# U64_KB_Ada.net
KiCad netlist of a schematic drawn in EAGLE
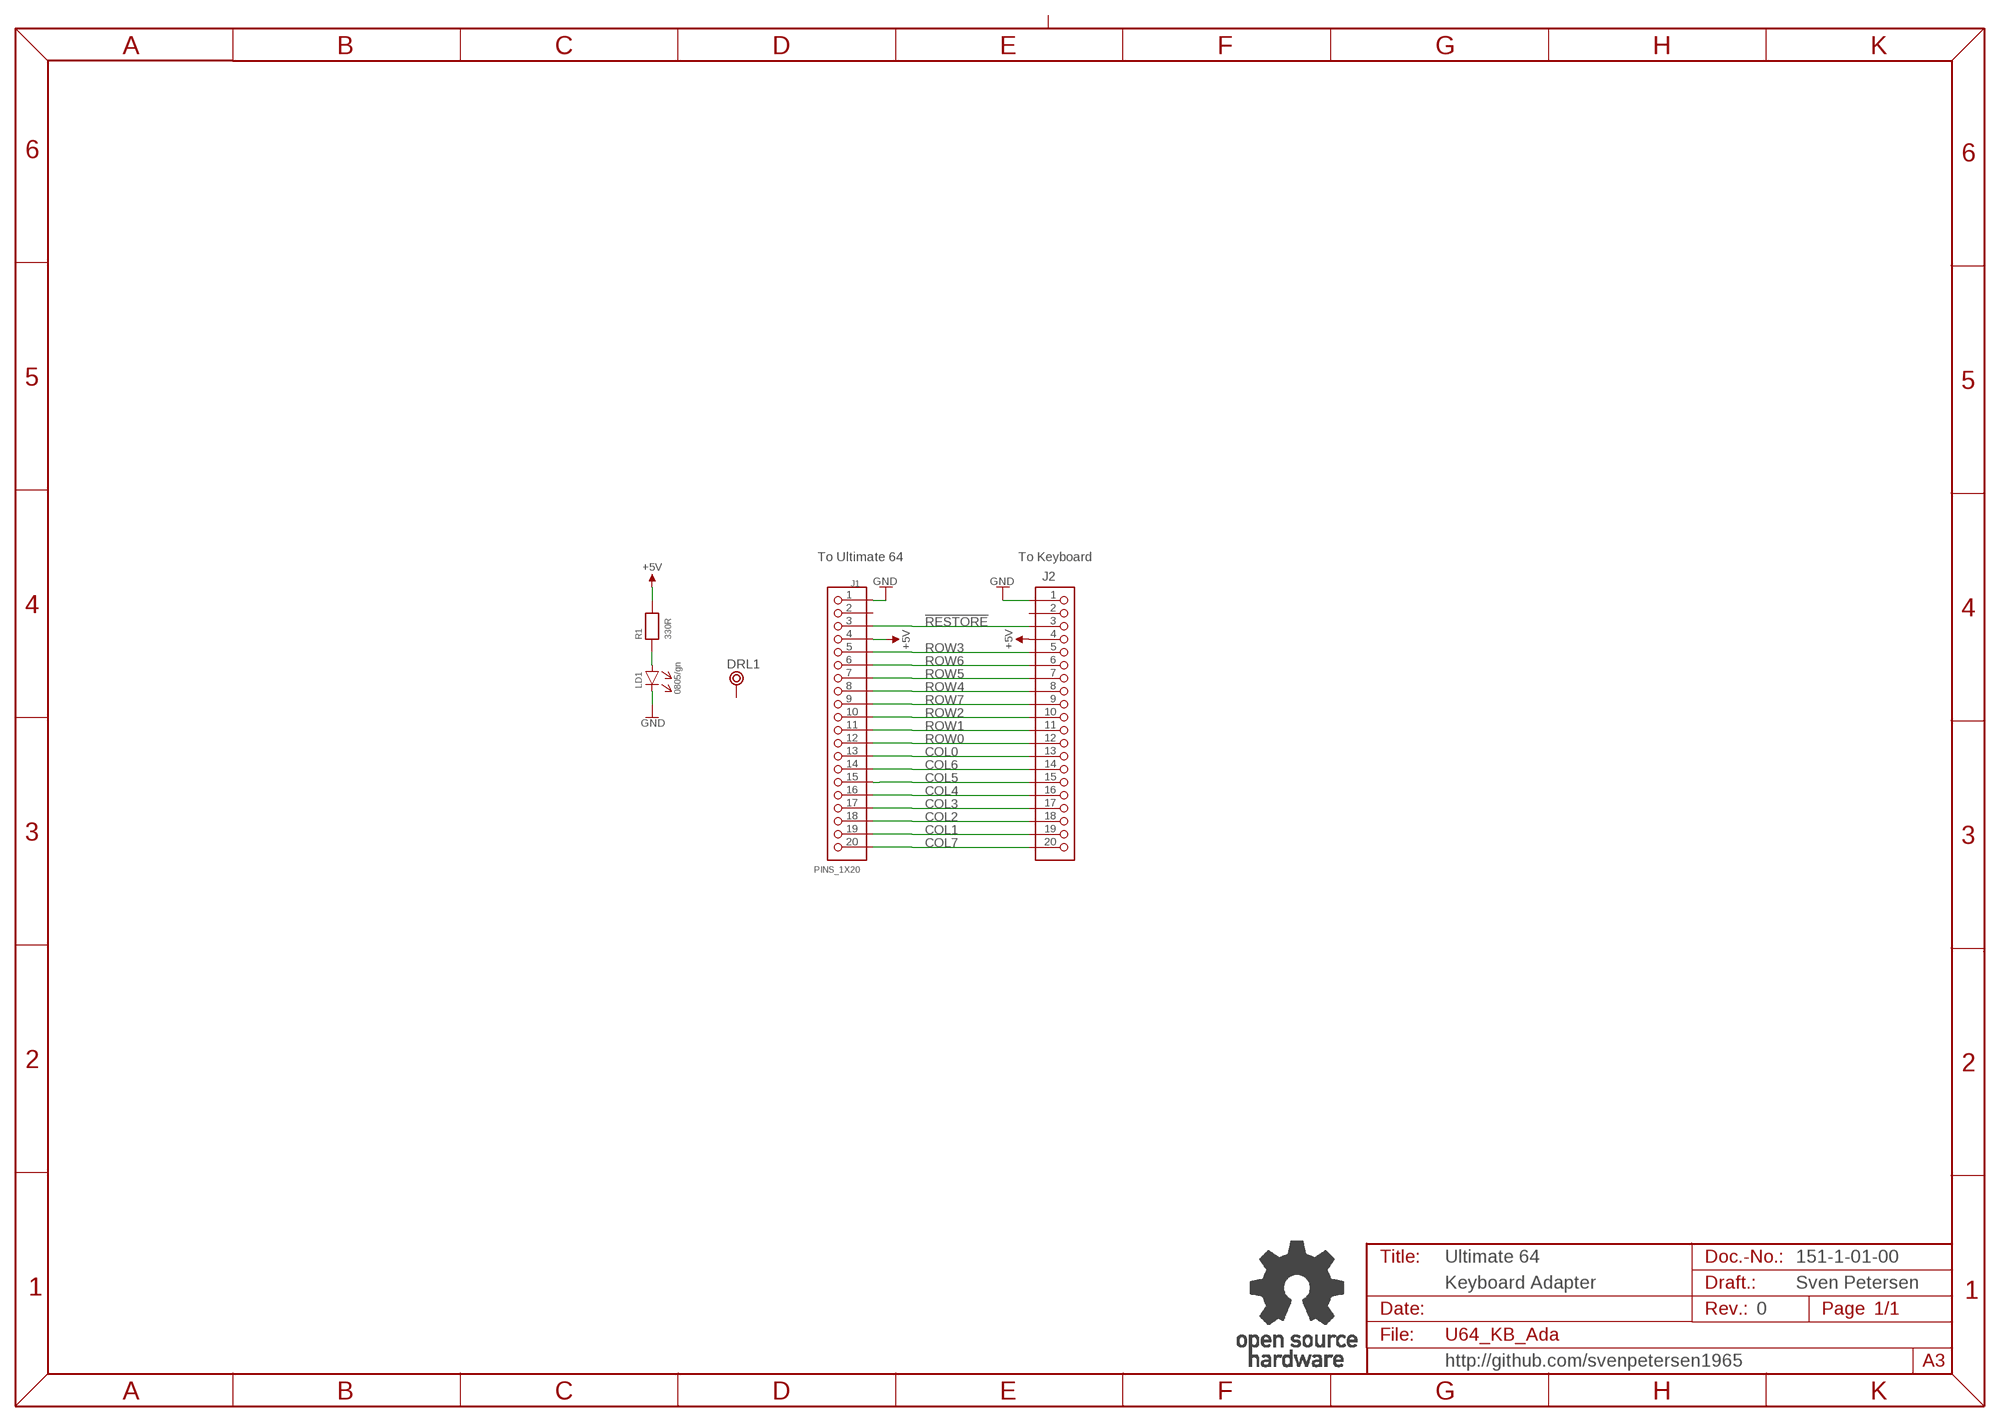
[diagram p0: schematic, sheet 1]

(export (version "E")
  (design (tool "Eeschema 10.0.6"))
  (components
    (comp (ref "DRL1")
      (value "BOHR3,5")
      (footprint "eagle-import:BOHR3,5")
      (libsource (lib "eagle-import") (part "BOHR3,5"))
    )
    (comp (ref "J1")
      (value "PINS_1X20")
      (footprint "eagle-import:PINS_1X20V")
      (libsource (lib "eagle-import") (part "PINS_1X20"))
    )
    (comp (ref "J2")
      (value "PINHD-1X20")
      (footprint "eagle-import:1X20")
      (libsource (lib "eagle-import") (part "PINHD-1X20"))
    )
    (comp (ref "LD1")
      (value "0805/gn")
      (footprint "eagle-import:0805")
      (libsource (lib "eagle-import") (part "0805-LED"))
    )
    (comp (ref "R1")
      (value "330R")
      (footprint "eagle-import:0805")
      (libsource (lib "eagle-import") (part "R-0805"))
    )
    (comp (ref "U$12")
      (value "OPEN_SOURCE_HW")
      (footprint "eagle-import:OPENHW")
      (libsource (lib "eagle-import") (part "OPEN_SOURCE_HW"))
    )
  )
  (nets
    (net (code "1") (name "+5V") (class "Default")
      (node (ref "J1") (pin "4") (pinfunction "4_4") (pintype "passive"))
      (node (ref "J2") (pin "4") (pinfunction "4_4") (pintype "passive"))
      (node (ref "R1") (pin "2") (pinfunction "2_2") (pintype "passive"))
    )
    (net (code "2") (name "/COL0") (class "Default")
      (node (ref "J1") (pin "13") (pinfunction "13_13") (pintype "passive"))
      (node (ref "J2") (pin "13") (pinfunction "13_13") (pintype "passive"))
    )
    (net (code "3") (name "/COL1") (class "Default")
      (node (ref "J1") (pin "19") (pinfunction "19_19") (pintype "passive"))
      (node (ref "J2") (pin "19") (pinfunction "19_19") (pintype "passive"))
    )
    (net (code "4") (name "/COL2") (class "Default")
      (node (ref "J1") (pin "18") (pinfunction "18_18") (pintype "passive"))
      (node (ref "J2") (pin "18") (pinfunction "18_18") (pintype "passive"))
    )
    (net (code "5") (name "/COL3") (class "Default")
      (node (ref "J1") (pin "17") (pinfunction "17_17") (pintype "passive"))
      (node (ref "J2") (pin "17") (pinfunction "17_17") (pintype "passive"))
    )
    (net (code "6") (name "/COL4") (class "Default")
      (node (ref "J1") (pin "16") (pinfunction "16_16") (pintype "passive"))
      (node (ref "J2") (pin "16") (pinfunction "16_16") (pintype "passive"))
    )
    (net (code "7") (name "/COL5") (class "Default")
      (node (ref "J1") (pin "15") (pinfunction "15_15") (pintype "passive"))
      (node (ref "J2") (pin "15") (pinfunction "15_15") (pintype "passive"))
    )
    (net (code "8") (name "/COL6") (class "Default")
      (node (ref "J1") (pin "14") (pinfunction "14_14") (pintype "passive"))
      (node (ref "J2") (pin "14") (pinfunction "14_14") (pintype "passive"))
    )
    (net (code "9") (name "/COL7") (class "Default")
      (node (ref "J1") (pin "20") (pinfunction "20_20") (pintype "passive"))
      (node (ref "J2") (pin "20") (pinfunction "20_20") (pintype "passive"))
    )
    (net (code "10") (name "/ROW0") (class "Default")
      (node (ref "J1") (pin "12") (pinfunction "12_12") (pintype "passive"))
      (node (ref "J2") (pin "12") (pinfunction "12_12") (pintype "passive"))
    )
    (net (code "11") (name "/ROW1") (class "Default")
      (node (ref "J1") (pin "11") (pinfunction "11_11") (pintype "passive"))
      (node (ref "J2") (pin "11") (pinfunction "11_11") (pintype "passive"))
    )
    (net (code "12") (name "/ROW2") (class "Default")
      (node (ref "J1") (pin "10") (pinfunction "10_10") (pintype "passive"))
      (node (ref "J2") (pin "10") (pinfunction "10_10") (pintype "passive"))
    )
    (net (code "13") (name "/ROW3") (class "Default")
      (node (ref "J1") (pin "5") (pinfunction "5_5") (pintype "passive"))
      (node (ref "J2") (pin "5") (pinfunction "5_5") (pintype "passive"))
    )
    (net (code "14") (name "/ROW4") (class "Default")
      (node (ref "J1") (pin "8") (pinfunction "8_8") (pintype "passive"))
      (node (ref "J2") (pin "8") (pinfunction "8_8") (pintype "passive"))
    )
    (net (code "15") (name "/ROW5") (class "Default")
      (node (ref "J1") (pin "7") (pinfunction "7_7") (pintype "passive"))
      (node (ref "J2") (pin "7") (pinfunction "7_7") (pintype "passive"))
    )
    (net (code "16") (name "/ROW6") (class "Default")
      (node (ref "J1") (pin "6") (pinfunction "6_6") (pintype "passive"))
      (node (ref "J2") (pin "6") (pinfunction "6_6") (pintype "passive"))
    )
    (net (code "17") (name "/ROW7") (class "Default")
      (node (ref "J1") (pin "9") (pinfunction "9_9") (pintype "passive"))
      (node (ref "J2") (pin "9") (pinfunction "9_9") (pintype "passive"))
    )
    (net (code "18") (name "/~{RESTORE}") (class "Default")
      (node (ref "J1") (pin "3") (pinfunction "3_3") (pintype "passive"))
      (node (ref "J2") (pin "3") (pinfunction "3_3") (pintype "passive"))
    )
    (net (code "19") (name "GND") (class "Default")
      (node (ref "J1") (pin "1") (pinfunction "1_1") (pintype "passive"))
      (node (ref "J2") (pin "1") (pinfunction "1_1") (pintype "passive"))
      (node (ref "LD1") (pin "K") (pinfunction "K_K") (pintype "bidirectional"))
    )
    (net (code "20") (name "Net-(LD1-PadA)") (class "Default")
      (node (ref "LD1") (pin "A") (pinfunction "A_A") (pintype "bidirectional"))
      (node (ref "R1") (pin "1") (pinfunction "1_1") (pintype "passive"))
    )
    (net (code "21") (name "unconnected-(DRL1-PadP$1)") (class "Default")
      (node (ref "DRL1") (pin "P$1") (pinfunction "P$1_P$1") (pintype "passive"))
    )
    (net (code "22") (name "unconnected-(J1-Pad2)") (class "Default")
      (node (ref "J1") (pin "2") (pinfunction "2_2") (pintype "passive"))
    )
    (net (code "23") (name "unconnected-(J2-Pad2)") (class "Default")
      (node (ref "J2") (pin "2") (pinfunction "2_2") (pintype "passive"))
    )
  )
)
